# ultrasonic.net
KiCad netlist of a schematic drawn in Altium Designer
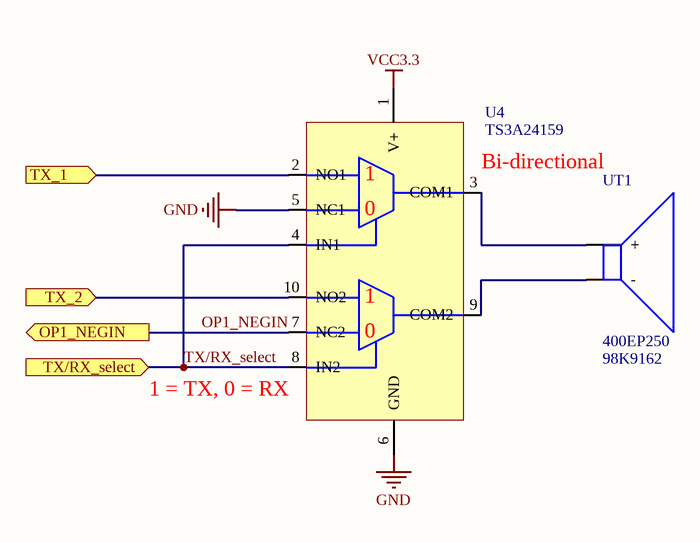
[diagram p0: ultrasonic.SchDoc]

(export (version "E")
  (design (tool "Eeschema 10.0.6"))
  (components
    (comp (ref "U4")
      (value "TS3A24159")
      (footprint "TSSOP50P490X110-10N")
      (description "DUAL-CHANNEL 2:1 MULTIPLEXER/DEMULTIPLEXER")
      (libsource (lib "ultrasounic") (part "TS3A24159"))
    )
    (comp (ref "UT1")
      (value "400EP250")
      (footprint "Transducer recepticle")
      (description "Air Ultrasounic Ceramic Transducers")
      (fields (field (name "SUPPLIER PART NUMBER 1") "98K9162"))
      (libsource (lib "ultrasounic") (part "Tranducer"))
    )
  )
  (nets
    (net (code "1") (name "/OP1_NEGIN") (class "Default")
      (node (ref "U4") (pin "7") (pinfunction "NC2_7") (pintype "passive"))
    )
    (net (code "2") (name "/TX_1") (class "Default")
      (node (ref "U4") (pin "2") (pinfunction "NO1_2") (pintype "passive"))
    )
    (net (code "3") (name "/TX_2") (class "Default")
      (node (ref "U4") (pin "10") (pinfunction "NO2_10") (pintype "passive"))
    )
    (net (code "4") (name "/TX{slash}RX_select") (class "Default")
      (node (ref "U4") (pin "4") (pinfunction "IN1_4") (pintype "passive"))
      (node (ref "U4") (pin "8") (pinfunction "IN2_8") (pintype "passive"))
    )
    (net (code "5") (name "GND") (class "Default")
      (node (ref "U4") (pin "5") (pinfunction "NC1_5") (pintype "passive"))
      (node (ref "U4") (pin "6") (pinfunction "GND_6") (pintype "passive"))
    )
    (net (code "6") (name "Net-(U4-COM1)") (class "Default")
      (node (ref "U4") (pin "3") (pinfunction "COM1_3") (pintype "passive"))
      (node (ref "UT1") (pin "2") (pinfunction "+_2") (pintype "passive"))
    )
    (net (code "7") (name "Net-(U4-COM2)") (class "Default")
      (node (ref "U4") (pin "9") (pinfunction "COM2_9") (pintype "passive"))
      (node (ref "UT1") (pin "1") (pinfunction "-_1") (pintype "passive"))
    )
    (net (code "8") (name "VCC3.3") (class "Default")
      (node (ref "U4") (pin "1") (pinfunction "V+_1") (pintype "passive"))
    )
  )
)
